# jerry_v1.net
KiCad netlist of a schematic drawn in EAGLE
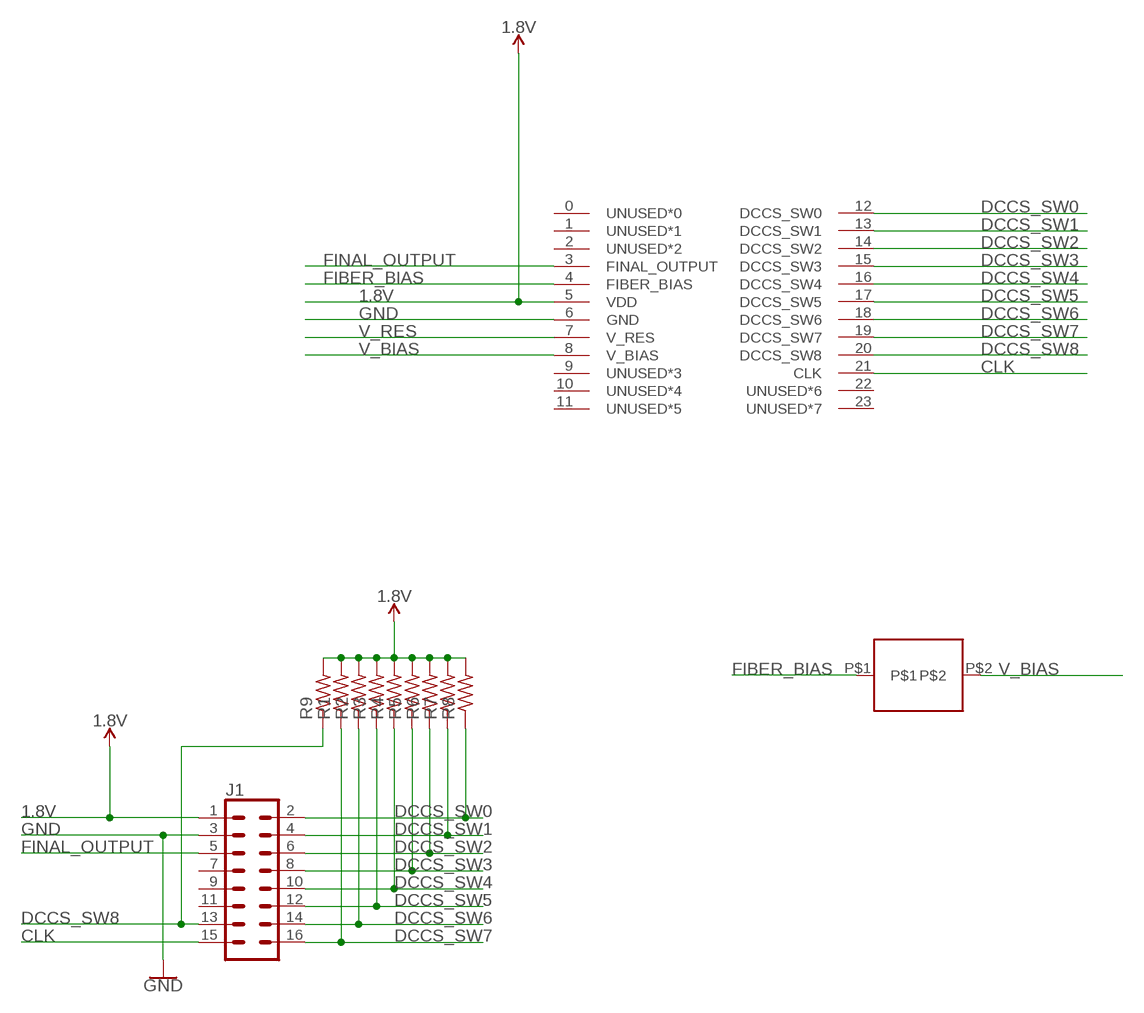
[diagram p0: schematic, sheet 1]

(export (version "E")
  (design (tool "Eeschema 10.0.6"))
  (components
    (comp (ref "J1")
      (value "CONN_08X2")
      (footprint "eagle-import:2X8")
      (libsource (lib "eagle-import") (part "CONN_08X2"))
    )
    (comp (ref "R1")
      (value "R-US_R0402")
      (footprint "eagle-import:R0402")
      (libsource (lib "eagle-import") (part "R-US_R0402"))
    )
    (comp (ref "R2")
      (value "R-US_R0402")
      (footprint "eagle-import:R0402")
      (libsource (lib "eagle-import") (part "R-US_R0402"))
    )
    (comp (ref "R3")
      (value "R-US_R0402")
      (footprint "eagle-import:R0402")
      (libsource (lib "eagle-import") (part "R-US_R0402"))
    )
    (comp (ref "R4")
      (value "R-US_R0402")
      (footprint "eagle-import:R0402")
      (libsource (lib "eagle-import") (part "R-US_R0402"))
    )
    (comp (ref "R5")
      (value "R-US_R0402")
      (footprint "eagle-import:R0402")
      (libsource (lib "eagle-import") (part "R-US_R0402"))
    )
    (comp (ref "R6")
      (value "R-US_R0402")
      (footprint "eagle-import:R0402")
      (libsource (lib "eagle-import") (part "R-US_R0402"))
    )
    (comp (ref "R7")
      (value "R-US_R0402")
      (footprint "eagle-import:R0402")
      (libsource (lib "eagle-import") (part "R-US_R0402"))
    )
    (comp (ref "R8")
      (value "R-US_R0402")
      (footprint "eagle-import:R0402")
      (libsource (lib "eagle-import") (part "R-US_R0402"))
    )
    (comp (ref "R9")
      (value "R-US_R0402")
      (footprint "eagle-import:R0402")
      (libsource (lib "eagle-import") (part "R-US_R0402"))
    )
    (comp (ref "U$1")
      (value "JERRY_V1")
      (footprint "eagle-import:JERRY_V1")
      (libsource (lib "eagle-import") (part "JERRY_V1"))
    )
    (comp (ref "U$2")
      (value "FIBER")
      (footprint "eagle-import:FIBER")
      (libsource (lib "eagle-import") (part "FIBER"))
    )
  )
  (nets
    (net (code "1") (name "/CLK") (class "Default")
      (node (ref "J1") (pin "15") (pinfunction "15_15") (pintype "passive"))
      (node (ref "U$1") (pin "21") (pinfunction "CLK_21") (pintype "bidirectional"))
    )
    (net (code "2") (name "/DCCS_SW0") (class "Default")
      (node (ref "J1") (pin "2") (pinfunction "2_2") (pintype "passive"))
      (node (ref "R8") (pin "1") (pinfunction "1_1") (pintype "passive"))
      (node (ref "U$1") (pin "12") (pinfunction "DCCS_SW0_12") (pintype "bidirectional"))
    )
    (net (code "3") (name "/DCCS_SW1") (class "Default")
      (node (ref "J1") (pin "4") (pinfunction "4_4") (pintype "passive"))
      (node (ref "R7") (pin "1") (pinfunction "1_1") (pintype "passive"))
      (node (ref "U$1") (pin "13") (pinfunction "DCCS_SW1_13") (pintype "bidirectional"))
    )
    (net (code "4") (name "/DCCS_SW2") (class "Default")
      (node (ref "J1") (pin "6") (pinfunction "6_6") (pintype "passive"))
      (node (ref "R6") (pin "1") (pinfunction "1_1") (pintype "passive"))
      (node (ref "U$1") (pin "14") (pinfunction "DCCS_SW2_14") (pintype "bidirectional"))
    )
    (net (code "5") (name "/DCCS_SW3") (class "Default")
      (node (ref "J1") (pin "8") (pinfunction "8_8") (pintype "passive"))
      (node (ref "R5") (pin "1") (pinfunction "1_1") (pintype "passive"))
      (node (ref "U$1") (pin "15") (pinfunction "DCCS_SW3_15") (pintype "bidirectional"))
    )
    (net (code "6") (name "/DCCS_SW4") (class "Default")
      (node (ref "J1") (pin "10") (pinfunction "10_10") (pintype "passive"))
      (node (ref "R4") (pin "1") (pinfunction "1_1") (pintype "passive"))
      (node (ref "U$1") (pin "16") (pinfunction "DCCS_SW4_16") (pintype "bidirectional"))
    )
    (net (code "7") (name "/DCCS_SW5") (class "Default")
      (node (ref "J1") (pin "12") (pinfunction "12_12") (pintype "passive"))
      (node (ref "R3") (pin "1") (pinfunction "1_1") (pintype "passive"))
      (node (ref "U$1") (pin "17") (pinfunction "DCCS_SW5_17") (pintype "bidirectional"))
    )
    (net (code "8") (name "/DCCS_SW6") (class "Default")
      (node (ref "J1") (pin "14") (pinfunction "14_14") (pintype "passive"))
      (node (ref "R2") (pin "1") (pinfunction "1_1") (pintype "passive"))
      (node (ref "U$1") (pin "18") (pinfunction "DCCS_SW6_18") (pintype "bidirectional"))
    )
    (net (code "9") (name "/DCCS_SW7") (class "Default")
      (node (ref "J1") (pin "16") (pinfunction "16_16") (pintype "passive"))
      (node (ref "R1") (pin "1") (pinfunction "1_1") (pintype "passive"))
      (node (ref "U$1") (pin "19") (pinfunction "DCCS_SW7_19") (pintype "bidirectional"))
    )
    (net (code "10") (name "/DCCS_SW8") (class "Default")
      (node (ref "J1") (pin "13") (pinfunction "13_13") (pintype "passive"))
      (node (ref "R9") (pin "1") (pinfunction "1_1") (pintype "passive"))
      (node (ref "U$1") (pin "20") (pinfunction "DCCS_SW8_20") (pintype "bidirectional"))
    )
    (net (code "11") (name "/FIBER_BIAS") (class "Default")
      (node (ref "U$1") (pin "4") (pinfunction "FIBER_BIAS_4") (pintype "bidirectional"))
      (node (ref "U$2") (pin "P$1") (pinfunction "P$1_P$1") (pintype "bidirectional"))
    )
    (net (code "12") (name "/FINAL_OUTPUT") (class "Default")
      (node (ref "J1") (pin "5") (pinfunction "5_5") (pintype "passive"))
      (node (ref "U$1") (pin "3") (pinfunction "FINAL_OUTPUT_3") (pintype "bidirectional"))
    )
    (net (code "13") (name "/V_BIAS") (class "Default")
      (node (ref "U$1") (pin "8") (pinfunction "V_BIAS_8") (pintype "bidirectional"))
      (node (ref "U$2") (pin "P$2") (pinfunction "P$2_P$2") (pintype "bidirectional"))
    )
    (net (code "14") (name "/V_RES") (class "Default")
      (node (ref "U$1") (pin "7") (pinfunction "V_RES_7") (pintype "bidirectional"))
    )
    (net (code "15") (name "1.8V") (class "Default")
      (node (ref "J1") (pin "1") (pinfunction "1_1") (pintype "passive"))
      (node (ref "R1") (pin "2") (pinfunction "2_2") (pintype "passive"))
      (node (ref "R2") (pin "2") (pinfunction "2_2") (pintype "passive"))
      (node (ref "R3") (pin "2") (pinfunction "2_2") (pintype "passive"))
      (node (ref "R4") (pin "2") (pinfunction "2_2") (pintype "passive"))
      (node (ref "R5") (pin "2") (pinfunction "2_2") (pintype "passive"))
      (node (ref "R6") (pin "2") (pinfunction "2_2") (pintype "passive"))
      (node (ref "R7") (pin "2") (pinfunction "2_2") (pintype "passive"))
      (node (ref "R8") (pin "2") (pinfunction "2_2") (pintype "passive"))
      (node (ref "R9") (pin "2") (pinfunction "2_2") (pintype "passive"))
      (node (ref "U$1") (pin "5") (pinfunction "VDD_5") (pintype "bidirectional"))
    )
    (net (code "16") (name "GND") (class "Default")
      (node (ref "J1") (pin "3") (pinfunction "3_3") (pintype "passive"))
      (node (ref "U$1") (pin "6") (pinfunction "GND_6") (pintype "bidirectional"))
    )
    (net (code "17") (name "unconnected-(J1-Pad7)") (class "Default")
      (node (ref "J1") (pin "7") (pinfunction "7_7") (pintype "passive"))
    )
    (net (code "18") (name "unconnected-(J1-Pad9)") (class "Default")
      (node (ref "J1") (pin "9") (pinfunction "9_9") (pintype "passive"))
    )
    (net (code "19") (name "unconnected-(J1-Pad11)") (class "Default")
      (node (ref "J1") (pin "11") (pinfunction "11_11") (pintype "passive"))
    )
    (net (code "20") (name "unconnected-(U$1-UNUSED*0-Pad0)") (class "Default")
      (node (ref "U$1") (pin "0") (pinfunction "UNUSED*0_0") (pintype "bidirectional"))
    )
    (net (code "21") (name "unconnected-(U$1-UNUSED*1-Pad1)") (class "Default")
      (node (ref "U$1") (pin "1") (pinfunction "UNUSED*1_1") (pintype "bidirectional"))
    )
    (net (code "22") (name "unconnected-(U$1-UNUSED*2-Pad2)") (class "Default")
      (node (ref "U$1") (pin "2") (pinfunction "UNUSED*2_2") (pintype "bidirectional"))
    )
    (net (code "23") (name "unconnected-(U$1-UNUSED*3-Pad9)") (class "Default")
      (node (ref "U$1") (pin "9") (pinfunction "UNUSED*3_9") (pintype "bidirectional"))
    )
    (net (code "24") (name "unconnected-(U$1-UNUSED*4-Pad10)") (class "Default")
      (node (ref "U$1") (pin "10") (pinfunction "UNUSED*4_10") (pintype "bidirectional"))
    )
    (net (code "25") (name "unconnected-(U$1-UNUSED*5-Pad11)") (class "Default")
      (node (ref "U$1") (pin "11") (pinfunction "UNUSED*5_11") (pintype "bidirectional"))
    )
    (net (code "26") (name "unconnected-(U$1-UNUSED*6-Pad22)") (class "Default")
      (node (ref "U$1") (pin "22") (pinfunction "UNUSED*6_22") (pintype "bidirectional"))
    )
    (net (code "27") (name "unconnected-(U$1-UNUSED*7-Pad23)") (class "Default")
      (node (ref "U$1") (pin "23") (pinfunction "UNUSED*7_23") (pintype "bidirectional"))
    )
  )
)
